# Memory.net
KiCad netlist of a schematic drawn in Altium Designer
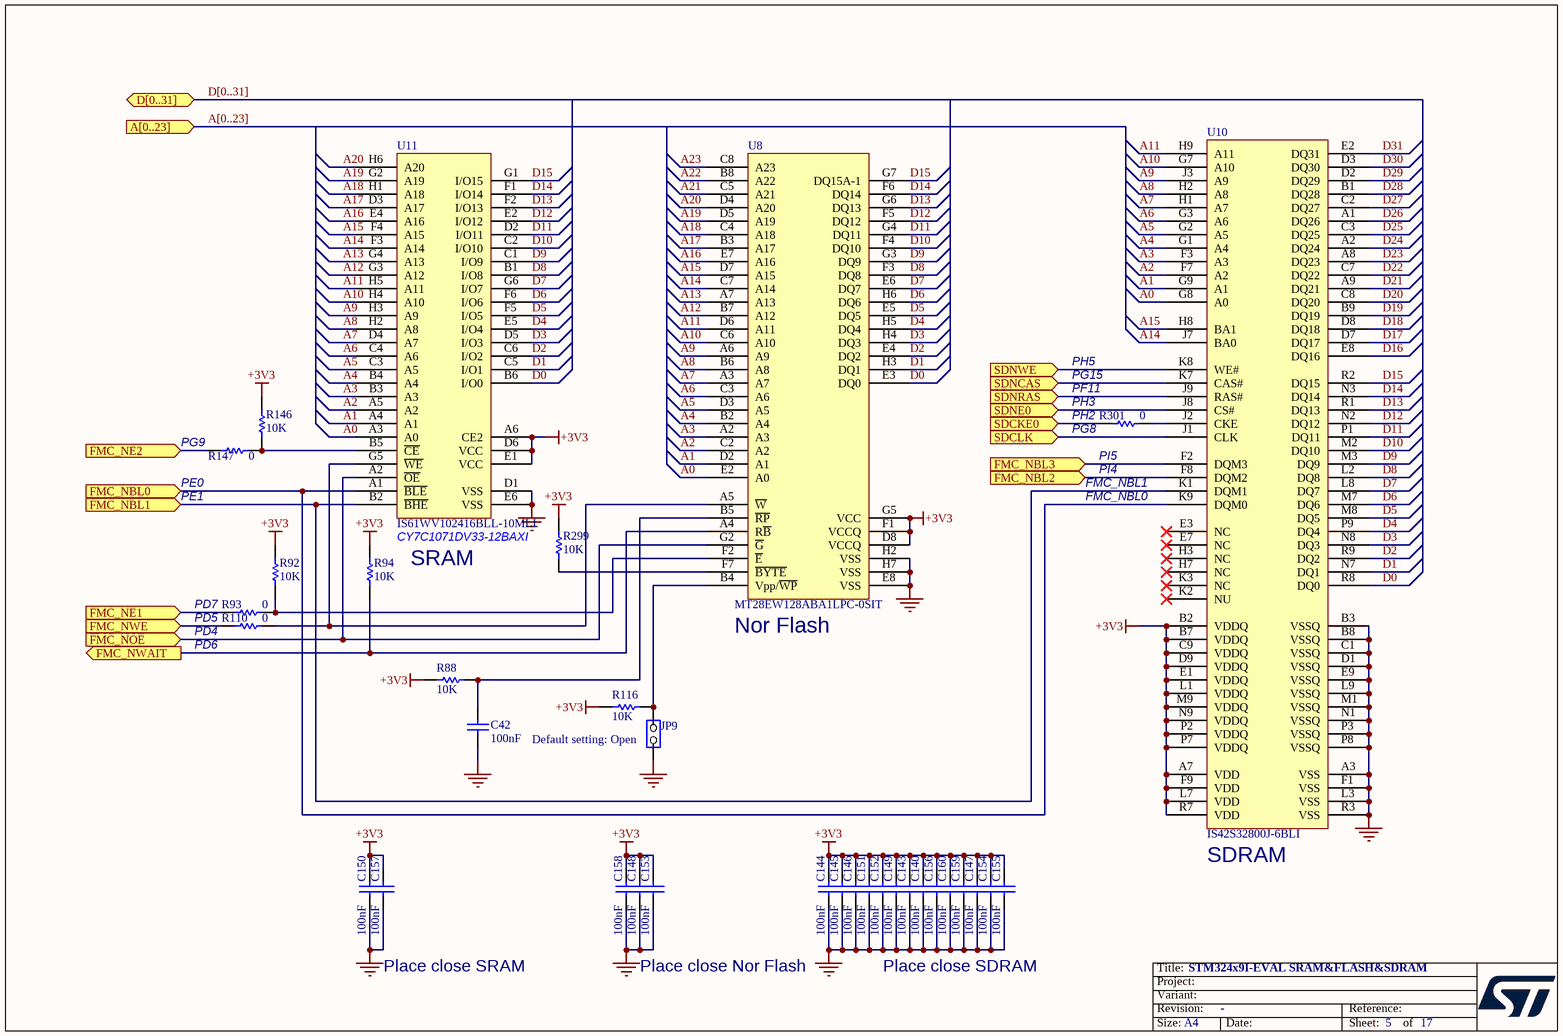
[diagram p0: Memory.SchDoc]

(export (version "E")
  (design (tool "Eeschema 10.0.6"))
  (components
    (comp (ref "C42")
      (value "100nF")
      (footprint "0603C")
      (description "Capacitor")
      (fields (field (name "PUBLISHER") "Altium Limited"))
      (libsource (lib "Miscellaneous Devices") (part "Cap"))
    )
    (comp (ref "C140")
      (value "100nF")
      (footprint "0603C")
      (description "Capacitor")
      (fields (field (name "PUBLISHER") "Altium Limited"))
      (libsource (lib "Miscellaneous Devices") (part "Cap"))
    )
    (comp (ref "C143")
      (value "100nF")
      (footprint "0603C")
      (description "Capacitor")
      (fields (field (name "PUBLISHER") "Altium Limited"))
      (libsource (lib "Miscellaneous Devices") (part "Cap"))
    )
    (comp (ref "C144")
      (value "100nF")
      (footprint "0603C")
      (description "Capacitor")
      (fields (field (name "PUBLISHER") "Altium Limited"))
      (libsource (lib "Miscellaneous Devices") (part "Cap"))
    )
    (comp (ref "C145")
      (value "100nF")
      (footprint "0603C")
      (description "Capacitor")
      (fields (field (name "PUBLISHER") "Altium Limited"))
      (libsource (lib "Miscellaneous Devices") (part "Cap"))
    )
    (comp (ref "C146")
      (value "100nF")
      (footprint "0603C")
      (description "Capacitor")
      (fields (field (name "PUBLISHER") "Altium Limited"))
      (libsource (lib "Miscellaneous Devices") (part "Cap"))
    )
    (comp (ref "C147")
      (value "100nF")
      (footprint "0603C")
      (description "Capacitor")
      (fields (field (name "PUBLISHER") "Altium Limited"))
      (libsource (lib "Miscellaneous Devices") (part "Cap"))
    )
    (comp (ref "C148")
      (value "100nF")
      (footprint "0603C")
      (description "Capacitor")
      (fields (field (name "PUBLISHER") "Altium Limited"))
      (libsource (lib "Miscellaneous Devices") (part "Cap"))
    )
    (comp (ref "C149")
      (value "100nF")
      (footprint "0603C")
      (description "Capacitor")
      (fields (field (name "PUBLISHER") "Altium Limited"))
      (libsource (lib "Miscellaneous Devices") (part "Cap"))
    )
    (comp (ref "C150")
      (value "100nF")
      (footprint "0603C")
      (description "Capacitor")
      (fields (field (name "PUBLISHER") "Altium Limited"))
      (libsource (lib "Miscellaneous Devices") (part "Cap"))
    )
    (comp (ref "C151")
      (value "100nF")
      (footprint "0603C")
      (description "Capacitor")
      (fields (field (name "PUBLISHER") "Altium Limited"))
      (libsource (lib "Miscellaneous Devices") (part "Cap"))
    )
    (comp (ref "C152")
      (value "100nF")
      (footprint "0603C")
      (description "Capacitor")
      (fields (field (name "PUBLISHER") "Altium Limited"))
      (libsource (lib "Miscellaneous Devices") (part "Cap"))
    )
    (comp (ref "C153")
      (value "100nF")
      (footprint "0603C")
      (description "Capacitor")
      (fields (field (name "PUBLISHER") "Altium Limited"))
      (libsource (lib "Miscellaneous Devices") (part "Cap"))
    )
    (comp (ref "C154")
      (value "100nF")
      (footprint "0603C")
      (description "Capacitor")
      (fields (field (name "PUBLISHER") "Altium Limited"))
      (libsource (lib "Miscellaneous Devices") (part "Cap"))
    )
    (comp (ref "C155")
      (value "100nF")
      (footprint "0603C")
      (description "Capacitor")
      (fields (field (name "PUBLISHER") "Altium Limited"))
      (libsource (lib "Miscellaneous Devices") (part "Cap"))
    )
    (comp (ref "C156")
      (value "100nF")
      (footprint "0603C")
      (description "Capacitor")
      (fields (field (name "PUBLISHER") "Altium Limited"))
      (libsource (lib "Miscellaneous Devices") (part "Cap"))
    )
    (comp (ref "C157")
      (value "100nF")
      (footprint "0603C")
      (description "Capacitor")
      (fields (field (name "PUBLISHER") "Altium Limited"))
      (libsource (lib "Miscellaneous Devices") (part "Cap"))
    )
    (comp (ref "C158")
      (value "100nF")
      (footprint "0603C")
      (description "Capacitor")
      (fields (field (name "PUBLISHER") "Altium Limited"))
      (libsource (lib "Miscellaneous Devices") (part "Cap"))
    )
    (comp (ref "C159")
      (value "100nF")
      (footprint "0603C")
      (description "Capacitor")
      (fields (field (name "PUBLISHER") "Altium Limited"))
      (libsource (lib "Miscellaneous Devices") (part "Cap"))
    )
    (comp (ref "C160")
      (value "100nF")
      (footprint "0603C")
      (description "Capacitor")
      (fields (field (name "PUBLISHER") "Altium Limited"))
      (libsource (lib "Miscellaneous Devices") (part "Cap"))
    )
    (comp (ref "JP9") (value "~") (footprint "SIP2") (libsource (lib "*") (part "JP2")))
    (comp (ref "R88")
      (value "10K")
      (footprint "0603R")
      (description "Resistor")
      (fields (field (name "PUBLISHER") "Altium Limited"))
      (libsource (lib "Miscellaneous Devices") (part "Res1"))
    )
    (comp (ref "R92")
      (value "10K")
      (footprint "0603R")
      (description "Resistor")
      (fields (field (name "PUBLISHER") "Altium Limited"))
      (libsource (lib "Miscellaneous Devices") (part "Res1"))
    )
    (comp (ref "R93")
      (value "0")
      (footprint "0603R")
      (description "Resistor")
      (fields (field (name "PUBLISHER") "Altium Limited"))
      (libsource (lib "Miscellaneous Devices") (part "Res1"))
    )
    (comp (ref "R94")
      (value "10K")
      (footprint "0603R")
      (description "Resistor")
      (fields (field (name "PUBLISHER") "Altium Limited"))
      (libsource (lib "Miscellaneous Devices") (part "Res1"))
    )
    (comp (ref "R110")
      (value "0")
      (footprint "0603R")
      (description "Resistor")
      (fields (field (name "PUBLISHER") "Altium Limited"))
      (libsource (lib "Miscellaneous Devices") (part "Res1"))
    )
    (comp (ref "R116")
      (value "10K")
      (footprint "0603R")
      (description "Resistor")
      (fields (field (name "PUBLISHER") "Altium Limited"))
      (libsource (lib "Miscellaneous Devices") (part "Res1"))
    )
    (comp (ref "R146")
      (value "10K")
      (footprint "0603R")
      (description "Resistor")
      (fields (field (name "PUBLISHER") "Altium Limited"))
      (libsource (lib "Miscellaneous Devices") (part "Res1"))
    )
    (comp (ref "R147")
      (value "0")
      (footprint "0603R")
      (description "Resistor")
      (fields (field (name "PUBLISHER") "Altium Limited"))
      (libsource (lib "Miscellaneous Devices") (part "Res1"))
    )
    (comp (ref "R299")
      (value "10K")
      (footprint "0603R")
      (description "Resistor")
      (fields (field (name "PUBLISHER") "Altium Limited"))
      (libsource (lib "Miscellaneous Devices") (part "Res1"))
    )
    (comp (ref "R301")
      (value "0")
      (footprint "0603R")
      (description "Resistor")
      (fields (field (name "PUBLISHER") "Altium Limited"))
      (libsource (lib "Miscellaneous Devices") (part "Res1"))
    )
    (comp (ref "U8")
      (value "MT28EW128ABA1LPC-0SIT")
      (footprint "BGA64_1_10X13")
      (description "IC,NOR FLASH 128Mbit 75ns - 64-ball LBGA")
      (libsource (lib "MB964") (part "M29W128FL70ZA6E"))
    )
    (comp (ref "U10")
      (value "IS42S32800J-6BLI")
      (footprint "FBGA90_0R8_8X13")
      (description "SDRAM 256MBit 166MHZ 90BGA")
      (libsource (lib "mb1045") (part "MT48LC4M32B2B5"))
    )
    (comp (ref "U11")
      (value "IS61WV102416BLL-10MLI")
      (footprint "BGA48_0R75_9X11")
      (libsource (lib "MB901") (part "IS61WV102416BLL-10MLI"))
    )
  )
  (nets
    (net (code "1") (name "+3V3") (class "Default")
      (node (ref "C140") (pin "1") (pinfunction "1_1") (pintype "passive"))
      (node (ref "C143") (pin "1") (pinfunction "1_1") (pintype "passive"))
      (node (ref "C144") (pin "1") (pinfunction "1_1") (pintype "passive"))
      (node (ref "C145") (pin "1") (pinfunction "1_1") (pintype "passive"))
      (node (ref "C146") (pin "1") (pinfunction "1_1") (pintype "passive"))
      (node (ref "C147") (pin "1") (pinfunction "1_1") (pintype "passive"))
      (node (ref "C148") (pin "1") (pinfunction "1_1") (pintype "passive"))
      (node (ref "C149") (pin "1") (pinfunction "1_1") (pintype "passive"))
      (node (ref "C150") (pin "1") (pinfunction "1_1") (pintype "passive"))
      (node (ref "C151") (pin "1") (pinfunction "1_1") (pintype "passive"))
      (node (ref "C152") (pin "1") (pinfunction "1_1") (pintype "passive"))
      (node (ref "C153") (pin "1") (pinfunction "1_1") (pintype "passive"))
      (node (ref "C154") (pin "1") (pinfunction "1_1") (pintype "passive"))
      (node (ref "C155") (pin "1") (pinfunction "1_1") (pintype "passive"))
      (node (ref "C156") (pin "1") (pinfunction "1_1") (pintype "passive"))
      (node (ref "C157") (pin "1") (pinfunction "1_1") (pintype "passive"))
      (node (ref "C158") (pin "1") (pinfunction "1_1") (pintype "passive"))
      (node (ref "C159") (pin "1") (pinfunction "1_1") (pintype "passive"))
      (node (ref "C160") (pin "1") (pinfunction "1_1") (pintype "passive"))
      (node (ref "R116") (pin "2") (pinfunction "2_2") (pintype "passive"))
      (node (ref "R146") (pin "2") (pinfunction "2_2") (pintype "passive"))
      (node (ref "R299") (pin "2") (pinfunction "2_2") (pintype "passive"))
      (node (ref "R88") (pin "1") (pinfunction "1_1") (pintype "passive"))
      (node (ref "R92") (pin "2") (pinfunction "2_2") (pintype "passive"))
      (node (ref "R94") (pin "2") (pinfunction "2_2") (pintype "passive"))
      (node (ref "U10") (pin "A7") (pinfunction "VDD_A7") (pintype "passive"))
      (node (ref "U10") (pin "B2") (pinfunction "VDDQ_B2") (pintype "passive"))
      (node (ref "U10") (pin "B7") (pinfunction "VDDQ_B7") (pintype "passive"))
      (node (ref "U10") (pin "C9") (pinfunction "VDDQ_C9") (pintype "passive"))
      (node (ref "U10") (pin "D9") (pinfunction "VDDQ_D9") (pintype "passive"))
      (node (ref "U10") (pin "E1") (pinfunction "VDDQ_E1") (pintype "passive"))
      (node (ref "U10") (pin "F9") (pinfunction "VDD_F9") (pintype "passive"))
      (node (ref "U10") (pin "L1") (pinfunction "VDDQ_L1") (pintype "passive"))
      (node (ref "U10") (pin "L7") (pinfunction "VDD_L7") (pintype "passive"))
      (node (ref "U10") (pin "M9") (pinfunction "VDDQ_M9") (pintype "passive"))
      (node (ref "U10") (pin "N9") (pinfunction "VDDQ_N9") (pintype "passive"))
      (node (ref "U10") (pin "P2") (pinfunction "VDDQ_P2") (pintype "passive"))
      (node (ref "U10") (pin "P7") (pinfunction "VDDQ_P7") (pintype "passive"))
      (node (ref "U10") (pin "R7") (pinfunction "VDD_R7") (pintype "passive"))
      (node (ref "U11") (pin "A6") (pinfunction "CE2_A6") (pintype "passive"))
      (node (ref "U11") (pin "D6") (pinfunction "VCC_D6") (pintype "passive"))
      (node (ref "U11") (pin "E1") (pinfunction "VCC_E1") (pintype "passive"))
      (node (ref "U8") (pin "D8") (pinfunction "VCCQ_D8") (pintype "passive"))
      (node (ref "U8") (pin "F1") (pinfunction "VCCQ_F1") (pintype "passive"))
      (node (ref "U8") (pin "G5") (pinfunction "VCC_G5") (pintype "passive"))
    )
    (net (code "2") (name "/A0") (class "Default")
      (node (ref "U10") (pin "G8") (pinfunction "A0_G8") (pintype "passive"))
      (node (ref "U11") (pin "A3") (pinfunction "A0_A3") (pintype "passive"))
      (node (ref "U8") (pin "E2") (pinfunction "A0_E2") (pintype "passive"))
    )
    (net (code "3") (name "/A1") (class "Default")
      (node (ref "U10") (pin "G9") (pinfunction "A1_G9") (pintype "passive"))
      (node (ref "U11") (pin "A4") (pinfunction "A1_A4") (pintype "passive"))
      (node (ref "U8") (pin "D2") (pinfunction "A1_D2") (pintype "passive"))
    )
    (net (code "4") (name "/A2") (class "Default")
      (node (ref "U10") (pin "F7") (pinfunction "A2_F7") (pintype "passive"))
      (node (ref "U11") (pin "A5") (pinfunction "A2_A5") (pintype "passive"))
      (node (ref "U8") (pin "C2") (pinfunction "A2_C2") (pintype "passive"))
    )
    (net (code "5") (name "/A3") (class "Default")
      (node (ref "U10") (pin "F3") (pinfunction "A3_F3") (pintype "passive"))
      (node (ref "U11") (pin "B3") (pinfunction "A3_B3") (pintype "passive"))
      (node (ref "U8") (pin "A2") (pinfunction "A3_A2") (pintype "passive"))
    )
    (net (code "6") (name "/A4") (class "Default")
      (node (ref "U10") (pin "G1") (pinfunction "A4_G1") (pintype "passive"))
      (node (ref "U11") (pin "B4") (pinfunction "A4_B4") (pintype "passive"))
      (node (ref "U8") (pin "B2") (pinfunction "A4_B2") (pintype "passive"))
    )
    (net (code "7") (name "/A5") (class "Default")
      (node (ref "U10") (pin "G2") (pinfunction "A5_G2") (pintype "passive"))
      (node (ref "U11") (pin "C3") (pinfunction "A5_C3") (pintype "passive"))
      (node (ref "U8") (pin "D3") (pinfunction "A5_D3") (pintype "passive"))
    )
    (net (code "8") (name "/A6") (class "Default")
      (node (ref "U10") (pin "G3") (pinfunction "A6_G3") (pintype "passive"))
      (node (ref "U11") (pin "C4") (pinfunction "A6_C4") (pintype "passive"))
      (node (ref "U8") (pin "C3") (pinfunction "A6_C3") (pintype "passive"))
    )
    (net (code "9") (name "/A7") (class "Default")
      (node (ref "U10") (pin "H1") (pinfunction "A7_H1") (pintype "passive"))
      (node (ref "U11") (pin "D4") (pinfunction "A7_D4") (pintype "passive"))
      (node (ref "U8") (pin "A3") (pinfunction "A7_A3") (pintype "passive"))
    )
    (net (code "10") (name "/A8") (class "Default")
      (node (ref "U10") (pin "H2") (pinfunction "A8_H2") (pintype "passive"))
      (node (ref "U11") (pin "H2") (pinfunction "A8_H2") (pintype "passive"))
      (node (ref "U8") (pin "B6") (pinfunction "A8_B6") (pintype "passive"))
    )
    (net (code "11") (name "/A9") (class "Default")
      (node (ref "U10") (pin "J3") (pinfunction "A9_J3") (pintype "passive"))
      (node (ref "U11") (pin "H3") (pinfunction "A9_H3") (pintype "passive"))
      (node (ref "U8") (pin "A6") (pinfunction "A9_A6") (pintype "passive"))
    )
    (net (code "12") (name "/A10") (class "Default")
      (node (ref "U10") (pin "G7") (pinfunction "A10_G7") (pintype "passive"))
      (node (ref "U11") (pin "H4") (pinfunction "A10_H4") (pintype "passive"))
      (node (ref "U8") (pin "C6") (pinfunction "A10_C6") (pintype "passive"))
    )
    (net (code "13") (name "/A11") (class "Default")
      (node (ref "U10") (pin "H9") (pinfunction "A11_H9") (pintype "passive"))
      (node (ref "U11") (pin "H5") (pinfunction "A11_H5") (pintype "passive"))
      (node (ref "U8") (pin "D6") (pinfunction "A11_D6") (pintype "passive"))
    )
    (net (code "14") (name "/A12") (class "Default")
      (node (ref "U11") (pin "G3") (pinfunction "A12_G3") (pintype "passive"))
      (node (ref "U8") (pin "B7") (pinfunction "A12_B7") (pintype "passive"))
    )
    (net (code "15") (name "/A13") (class "Default")
      (node (ref "U11") (pin "G4") (pinfunction "A13_G4") (pintype "passive"))
      (node (ref "U8") (pin "A7") (pinfunction "A13_A7") (pintype "passive"))
    )
    (net (code "16") (name "/A14") (class "Default")
      (node (ref "U10") (pin "J7") (pinfunction "BA0_J7") (pintype "passive"))
      (node (ref "U11") (pin "F3") (pinfunction "A14_F3") (pintype "passive"))
      (node (ref "U8") (pin "C7") (pinfunction "A14_C7") (pintype "passive"))
    )
    (net (code "17") (name "/A15") (class "Default")
      (node (ref "U10") (pin "H8") (pinfunction "BA1_H8") (pintype "passive"))
      (node (ref "U11") (pin "F4") (pinfunction "A15_F4") (pintype "passive"))
      (node (ref "U8") (pin "D7") (pinfunction "A15_D7") (pintype "passive"))
    )
    (net (code "18") (name "/A16") (class "Default")
      (node (ref "U11") (pin "E4") (pinfunction "A16_E4") (pintype "passive"))
      (node (ref "U8") (pin "E7") (pinfunction "A16_E7") (pintype "passive"))
    )
    (net (code "19") (name "/A17") (class "Default")
      (node (ref "U11") (pin "D3") (pinfunction "A17_D3") (pintype "passive"))
      (node (ref "U8") (pin "B3") (pinfunction "A17_B3") (pintype "passive"))
    )
    (net (code "20") (name "/A18") (class "Default")
      (node (ref "U11") (pin "H1") (pinfunction "A18_H1") (pintype "passive"))
      (node (ref "U8") (pin "C4") (pinfunction "A18_C4") (pintype "passive"))
    )
    (net (code "21") (name "/A19") (class "Default")
      (node (ref "U11") (pin "G2") (pinfunction "A19_G2") (pintype "passive"))
      (node (ref "U8") (pin "D5") (pinfunction "A19_D5") (pintype "passive"))
    )
    (net (code "22") (name "/A20") (class "Default")
      (node (ref "U11") (pin "H6") (pinfunction "A20_H6") (pintype "passive"))
      (node (ref "U8") (pin "D4") (pinfunction "A20_D4") (pintype "passive"))
    )
    (net (code "23") (name "/A21") (class "Default")
      (node (ref "U8") (pin "C5") (pinfunction "A21_C5") (pintype "passive"))
    )
    (net (code "24") (name "/A22") (class "Default")
      (node (ref "U8") (pin "B8") (pinfunction "A22_B8") (pintype "passive"))
    )
    (net (code "25") (name "/A23") (class "Default")
      (node (ref "U8") (pin "C8") (pinfunction "A23_C8") (pintype "passive"))
    )
    (net (code "27") (name "/D0") (class "Default")
      (node (ref "U10") (pin "R8") (pinfunction "DQ0_R8") (pintype "passive"))
      (node (ref "U11") (pin "B6") (pinfunction "I/O0_B6") (pintype "passive"))
      (node (ref "U8") (pin "E3") (pinfunction "DQ0_E3") (pintype "passive"))
    )
    (net (code "28") (name "/D1") (class "Default")
      (node (ref "U10") (pin "N7") (pinfunction "DQ1_N7") (pintype "passive"))
      (node (ref "U11") (pin "C5") (pinfunction "I/O1_C5") (pintype "passive"))
      (node (ref "U8") (pin "H3") (pinfunction "DQ1_H3") (pintype "passive"))
    )
    (net (code "29") (name "/D2") (class "Default")
      (node (ref "U10") (pin "R9") (pinfunction "DQ2_R9") (pintype "passive"))
      (node (ref "U11") (pin "C6") (pinfunction "I/O2_C6") (pintype "passive"))
      (node (ref "U8") (pin "E4") (pinfunction "DQ2_E4") (pintype "passive"))
    )
    (net (code "30") (name "/D3") (class "Default")
      (node (ref "U10") (pin "N8") (pinfunction "DQ3_N8") (pintype "passive"))
      (node (ref "U11") (pin "D5") (pinfunction "I/O3_D5") (pintype "passive"))
      (node (ref "U8") (pin "H4") (pinfunction "DQ3_H4") (pintype "passive"))
    )
    (net (code "31") (name "/D4") (class "Default")
      (node (ref "U10") (pin "P9") (pinfunction "DQ4_P9") (pintype "passive"))
      (node (ref "U11") (pin "E5") (pinfunction "I/O4_E5") (pintype "passive"))
      (node (ref "U8") (pin "H5") (pinfunction "DQ4_H5") (pintype "passive"))
    )
    (net (code "32") (name "/D5") (class "Default")
      (node (ref "U10") (pin "M8") (pinfunction "DQ5_M8") (pintype "passive"))
      (node (ref "U11") (pin "F5") (pinfunction "I/O5_F5") (pintype "passive"))
      (node (ref "U8") (pin "E5") (pinfunction "DQ5_E5") (pintype "passive"))
    )
    (net (code "33") (name "/D6") (class "Default")
      (node (ref "U10") (pin "M7") (pinfunction "DQ6_M7") (pintype "passive"))
      (node (ref "U11") (pin "F6") (pinfunction "I/O6_F6") (pintype "passive"))
      (node (ref "U8") (pin "H6") (pinfunction "DQ6_H6") (pintype "passive"))
    )
    (net (code "34") (name "/D7") (class "Default")
      (node (ref "U10") (pin "L8") (pinfunction "DQ7_L8") (pintype "passive"))
      (node (ref "U11") (pin "G6") (pinfunction "I/O7_G6") (pintype "passive"))
      (node (ref "U8") (pin "E6") (pinfunction "DQ7_E6") (pintype "passive"))
    )
    (net (code "35") (name "/D8") (class "Default")
      (node (ref "U10") (pin "L2") (pinfunction "DQ8_L2") (pintype "passive"))
      (node (ref "U11") (pin "B1") (pinfunction "I/O8_B1") (pintype "passive"))
      (node (ref "U8") (pin "F3") (pinfunction "DQ8_F3") (pintype "passive"))
    )
    (net (code "36") (name "/D9") (class "Default")
      (node (ref "U10") (pin "M3") (pinfunction "DQ9_M3") (pintype "passive"))
      (node (ref "U11") (pin "C1") (pinfunction "I/O9_C1") (pintype "passive"))
      (node (ref "U8") (pin "G3") (pinfunction "DQ9_G3") (pintype "passive"))
    )
    (net (code "37") (name "/D10") (class "Default")
      (node (ref "U10") (pin "M2") (pinfunction "DQ10_M2") (pintype "passive"))
      (node (ref "U11") (pin "C2") (pinfunction "I/O10_C2") (pintype "passive"))
      (node (ref "U8") (pin "F4") (pinfunction "DQ10_F4") (pintype "passive"))
    )
    (net (code "38") (name "/D11") (class "Default")
      (node (ref "U10") (pin "P1") (pinfunction "DQ11_P1") (pintype "passive"))
      (node (ref "U11") (pin "D2") (pinfunction "I/O11_D2") (pintype "passive"))
      (node (ref "U8") (pin "G4") (pinfunction "DQ11_G4") (pintype "passive"))
    )
    (net (code "39") (name "/D12") (class "Default")
      (node (ref "U10") (pin "N2") (pinfunction "DQ12_N2") (pintype "passive"))
      (node (ref "U11") (pin "E2") (pinfunction "I/O12_E2") (pintype "passive"))
      (node (ref "U8") (pin "F5") (pinfunction "DQ12_F5") (pintype "passive"))
    )
    (net (code "40") (name "/D13") (class "Default")
      (node (ref "U10") (pin "R1") (pinfunction "DQ13_R1") (pintype "passive"))
      (node (ref "U11") (pin "F2") (pinfunction "I/O13_F2") (pintype "passive"))
      (node (ref "U8") (pin "G6") (pinfunction "DQ13_G6") (pintype "passive"))
    )
    (net (code "41") (name "/D14") (class "Default")
      (node (ref "U10") (pin "N3") (pinfunction "DQ14_N3") (pintype "passive"))
      (node (ref "U11") (pin "F1") (pinfunction "I/O14_F1") (pintype "passive"))
      (node (ref "U8") (pin "F6") (pinfunction "DQ14_F6") (pintype "passive"))
    )
    (net (code "42") (name "/D15") (class "Default")
      (node (ref "U10") (pin "R2") (pinfunction "DQ15_R2") (pintype "passive"))
      (node (ref "U11") (pin "G1") (pinfunction "I/O15_G1") (pintype "passive"))
      (node (ref "U8") (pin "G7") (pinfunction "DQ15A-1_G7") (pintype "passive"))
    )
    (net (code "43") (name "/D16") (class "Default")
      (node (ref "U10") (pin "E8") (pinfunction "DQ16_E8") (pintype "passive"))
    )
    (net (code "44") (name "/D17") (class "Default")
      (node (ref "U10") (pin "D7") (pinfunction "DQ17_D7") (pintype "passive"))
    )
    (net (code "45") (name "/D18") (class "Default")
      (node (ref "U10") (pin "D8") (pinfunction "DQ18_D8") (pintype "passive"))
    )
    (net (code "46") (name "/D19") (class "Default")
      (node (ref "U10") (pin "B9") (pinfunction "DQ19_B9") (pintype "passive"))
    )
    (net (code "47") (name "/D20") (class "Default")
      (node (ref "U10") (pin "C8") (pinfunction "DQ20_C8") (pintype "passive"))
    )
    (net (code "48") (name "/D21") (class "Default")
      (node (ref "U10") (pin "A9") (pinfunction "DQ21_A9") (pintype "passive"))
    )
    (net (code "49") (name "/D22") (class "Default")
      (node (ref "U10") (pin "C7") (pinfunction "DQ22_C7") (pintype "passive"))
    )
    (net (code "50") (name "/D23") (class "Default")
      (node (ref "U10") (pin "A8") (pinfunction "DQ23_A8") (pintype "passive"))
    )
    (net (code "51") (name "/D24") (class "Default")
      (node (ref "U10") (pin "A2") (pinfunction "DQ24_A2") (pintype "passive"))
    )
    (net (code "52") (name "/D25") (class "Default")
      (node (ref "U10") (pin "C3") (pinfunction "DQ25_C3") (pintype "passive"))
    )
    (net (code "53") (name "/D26") (class "Default")
      (node (ref "U10") (pin "A1") (pinfunction "DQ26_A1") (pintype "passive"))
    )
    (net (code "54") (name "/D27") (class "Default")
      (node (ref "U10") (pin "C2") (pinfunction "DQ27_C2") (pintype "passive"))
    )
    (net (code "55") (name "/D28") (class "Default")
      (node (ref "U10") (pin "B1") (pinfunction "DQ28_B1") (pintype "passive"))
    )
    (net (code "56") (name "/D29") (class "Default")
      (node (ref "U10") (pin "D2") (pinfunction "DQ29_D2") (pintype "passive"))
    )
    (net (code "57") (name "/D30") (class "Default")
      (node (ref "U10") (pin "D3") (pinfunction "DQ30_D3") (pintype "passive"))
    )
    (net (code "58") (name "/D31") (class "Default")
      (node (ref "U10") (pin "E2") (pinfunction "DQ31_E2") (pintype "passive"))
    )
    (net (code "60") (name "/FMC_NBL0") (class "Default")
      (node (ref "U10") (pin "K9") (pinfunction "DQM0_K9") (pintype "passive"))
      (node (ref "U11") (pin "A1") (pinfunction "~{BLE}_A1") (pintype "passive"))
    )
    (net (code "61") (name "/FMC_NBL1") (class "Default")
      (node (ref "U10") (pin "K1") (pinfunction "DQM1_K1") (pintype "passive"))
      (node (ref "U11") (pin "B2") (pinfunction "~{BHE}_B2") (pintype "passive"))
    )
    (net (code "62") (name "/FMC_NBL2") (class "Default")
      (node (ref "U10") (pin "F8") (pinfunction "DQM2_F8") (pintype "passive"))
    )
    (net (code "63") (name "/FMC_NBL3") (class "Default")
      (node (ref "U10") (pin "F2") (pinfunction "DQM3_F2") (pintype "passive"))
    )
    (net (code "64") (name "/FMC_NE1") (class "Default")
      (node (ref "R93") (pin "2") (pinfunction "2_2") (pintype "passive"))
    )
    (net (code "65") (name "/FMC_NE2") (class "Default")
      (node (ref "R147") (pin "2") (pinfunction "2_2") (pintype "passive"))
    )
    (net (code "66") (name "/FMC_NOE") (class "Default")
      (node (ref "U11") (pin "A2") (pinfunction "~{OE}_A2") (pintype "passive"))
      (node (ref "U8") (pin "G2") (pinfunction "~{G}_G2") (pintype "passive"))
    )
    (net (code "67") (name "/FMC_NWAIT") (class "Default")
      (node (ref "R94") (pin "1") (pinfunction "1_1") (pintype "passive"))
      (node (ref "U8") (pin "A4") (pinfunction "R~{B}_A4") (pintype "passive"))
    )
    (net (code "68") (name "/FMC_NWE") (class "Default")
      (node (ref "R110") (pin "2") (pinfunction "2_2") (pintype "passive"))
    )
    (net (code "69") (name "/SDCKE0") (class "Default")
      (node (ref "R301") (pin "2") (pinfunction "2_2") (pintype "passive"))
    )
    (net (code "70") (name "/SDCLK") (class "Default")
      (node (ref "U10") (pin "J1") (pinfunction "CLK_J1") (pintype "passive"))
    )
    (net (code "71") (name "/SDNCAS") (class "Default")
      (node (ref "U10") (pin "K7") (pinfunction "CAS#_K7") (pintype "passive"))
    )
    (net (code "72") (name "/SDNE0") (class "Default")
      (node (ref "U10") (pin "J8") (pinfunction "CS#_J8") (pintype "passive"))
    )
    (net (code "73") (name "/SDNRAS") (class "Default")
      (node (ref "U10") (pin "J9") (pinfunction "RAS#_J9") (pintype "passive"))
    )
    (net (code "74") (name "/SDNWE") (class "Default")
      (node (ref "U10") (pin "K8") (pinfunction "WE#_K8") (pintype "passive"))
    )
    (net (code "75") (name "GND") (class "Default")
      (node (ref "C140") (pin "2") (pinfunction "2_2") (pintype "passive"))
      (node (ref "C143") (pin "2") (pinfunction "2_2") (pintype "passive"))
      (node (ref "C144") (pin "2") (pinfunction "2_2") (pintype "passive"))
      (node (ref "C145") (pin "2") (pinfunction "2_2") (pintype "passive"))
      (node (ref "C146") (pin "2") (pinfunction "2_2") (pintype "passive"))
      (node (ref "C147") (pin "2") (pinfunction "2_2") (pintype "passive"))
      (node (ref "C148") (pin "2") (pinfunction "2_2") (pintype "passive"))
      (node (ref "C149") (pin "2") (pinfunction "2_2") (pintype "passive"))
      (node (ref "C150") (pin "2") (pinfunction "2_2") (pintype "passive"))
      (node (ref "C151") (pin "2") (pinfunction "2_2") (pintype "passive"))
      (node (ref "C152") (pin "2") (pinfunction "2_2") (pintype "passive"))
      (node (ref "C153") (pin "2") (pinfunction "2_2") (pintype "passive"))
      (node (ref "C154") (pin "2") (pinfunction "2_2") (pintype "passive"))
      (node (ref "C155") (pin "2") (pinfunction "2_2") (pintype "passive"))
      (node (ref "C156") (pin "2") (pinfunction "2_2") (pintype "passive"))
      (node (ref "C157") (pin "2") (pinfunction "2_2") (pintype "passive"))
      (node (ref "C158") (pin "2") (pinfunction "2_2") (pintype "passive"))
      (node (ref "C159") (pin "2") (pinfunction "2_2") (pintype "passive"))
      (node (ref "C160") (pin "2") (pinfunction "2_2") (pintype "passive"))
      (node (ref "C42") (pin "2") (pinfunction "2_2") (pintype "passive"))
      (node (ref "JP9") (pin "1") (pinfunction "COMMON_1") (pintype "passive"))
      (node (ref "U10") (pin "A3") (pinfunction "VSS_A3") (pintype "passive"))
      (node (ref "U10") (pin "B3") (pinfunction "VSSQ_B3") (pintype "passive"))
      (node (ref "U10") (pin "B8") (pinfunction "VSSQ_B8") (pintype "passive"))
      (node (ref "U10") (pin "C1") (pinfunction "VSSQ_C1") (pintype "passive"))
      (node (ref "U10") (pin "D1") (pinfunction "VSSQ_D1") (pintype "passive"))
      (node (ref "U10") (pin "E9") (pinfunction "VSSQ_E9") (pintype "passive"))
      (node (ref "U10") (pin "F1") (pinfunction "VSS_F1") (pintype "passive"))
      (node (ref "U10") (pin "L3") (pinfunction "VSS_L3") (pintype "passive"))
      (node (ref "U10") (pin "L9") (pinfunction "VSSQ_L9") (pintype "passive"))
      (node (ref "U10") (pin "M1") (pinfunction "VSSQ_M1") (pintype "passive"))
      (node (ref "U10") (pin "N1") (pinfunction "VSSQ_N1") (pintype "passive"))
      (node (ref "U10") (pin "P3") (pinfunction "VSSQ_P3") (pintype "passive"))
      (node (ref "U10") (pin "P8") (pinfunction "VSSQ_P8") (pintype "passive"))
      (node (ref "U10") (pin "R3") (pinfunction "VSS_R3") (pintype "passive"))
      (node (ref "U11") (pin "D1") (pinfunction "VSS_D1") (pintype "passive"))
      (node (ref "U11") (pin "E6") (pinfunction "VSS_E6") (pintype "passive"))
      (node (ref "U8") (pin "E8") (pinfunction "VSS_E8") (pintype "passive"))
      (node (ref "U8") (pin "H2") (pinfunction "VSS_H2") (pintype "passive"))
      (node (ref "U8") (pin "H7") (pinfunction "VSS_H7") (pintype "passive"))
    )
    (net (code "76") (name "Net-(JP9-NO)") (class "Default")
      (node (ref "JP9") (pin "2") (pinfunction "NO_2") (pintype "passive"))
      (node (ref "R116") (pin "1") (pinfunction "1_1") (pintype "passive"))
      (node (ref "U8") (pin "B4") (pinfunction "Vpp/~{WP}_B4") (pintype "passive"))
    )
    (net (code "77") (name "Net-(U8-~{BYTE})") (class "Default")
      (node (ref "R299") (pin "1") (pinfunction "1_1") (pintype "passive"))
      (node (ref "U8") (pin "F7") (pinfunction "~{BYTE}_F7") (pintype "passive"))
    )
    (net (code "78") (name "Net-(U8-~{E})") (class "Default")
      (node (ref "R92") (pin "1") (pinfunction "1_1") (pintype "passive"))
      (node (ref "R93") (pin "1") (pinfunction "1_1") (pintype "passive"))
      (node (ref "U8") (pin "F2") (pinfunction "~{E}_F2") (pintype "passive"))
    )
    (net (code "79") (name "Net-(U8-~{RP})") (class "Default")
      (node (ref "C42") (pin "1") (pinfunction "1_1") (pintype "passive"))
      (node (ref "R88") (pin "2") (pinfunction "2_2") (pintype "passive"))
      (node (ref "U8") (pin "B5") (pinfunction "~{RP}_B5") (pintype "passive"))
    )
    (net (code "80") (name "Net-(U10-CKE)") (class "Default")
      (node (ref "R301") (pin "1") (pinfunction "1_1") (pintype "passive"))
      (node (ref "U10") (pin "J2") (pinfunction "CKE_J2") (pintype "passive"))
    )
    (net (code "81") (name "Net-(U11-~{CE})") (class "Default")
      (node (ref "R146") (pin "1") (pinfunction "1_1") (pintype "passive"))
      (node (ref "R147") (pin "1") (pinfunction "1_1") (pintype "passive"))
      (node (ref "U11") (pin "B5") (pinfunction "~{CE}_B5") (pintype "passive"))
    )
    (net (code "82") (name "Net-(U11-~{WE})") (class "Default")
      (node (ref "R110") (pin "1") (pinfunction "1_1") (pintype "passive"))
      (node (ref "U11") (pin "G5") (pinfunction "~{WE}_G5") (pintype "passive"))
      (node (ref "U8") (pin "A5") (pinfunction "~{W}_A5") (pintype "passive"))
    )
    (net (code "83") (name "unconnected-(U10-NC-PadE3)") (class "Default")
      (node (ref "U10") (pin "E3") (pinfunction "NC_E3") (pintype "passive+no_connect"))
    )
    (net (code "84") (name "unconnected-(U10-NC-PadE7)") (class "Default")
      (node (ref "U10") (pin "E7") (pinfunction "NC_E7") (pintype "passive+no_connect"))
    )
    (net (code "85") (name "unconnected-(U10-NC-PadH3)") (class "Default")
      (node (ref "U10") (pin "H3") (pinfunction "NC_H3") (pintype "passive+no_connect"))
    )
    (net (code "86") (name "unconnected-(U10-NC-PadH7)") (class "Default")
      (node (ref "U10") (pin "H7") (pinfunction "NC_H7") (pintype "passive+no_connect"))
    )
    (net (code "87") (name "unconnected-(U10-NC-PadK3)") (class "Default")
      (node (ref "U10") (pin "K3") (pinfunction "NC_K3") (pintype "passive+no_connect"))
    )
    (net (code "88") (name "unconnected-(U10-NU-PadK2)") (class "Default")
      (node (ref "U10") (pin "K2") (pinfunction "NU_K2") (pintype "passive+no_connect"))
    )
  )
)
